# Vario_sch.net
KiCad netlist of a schematic drawn in Altium Designer
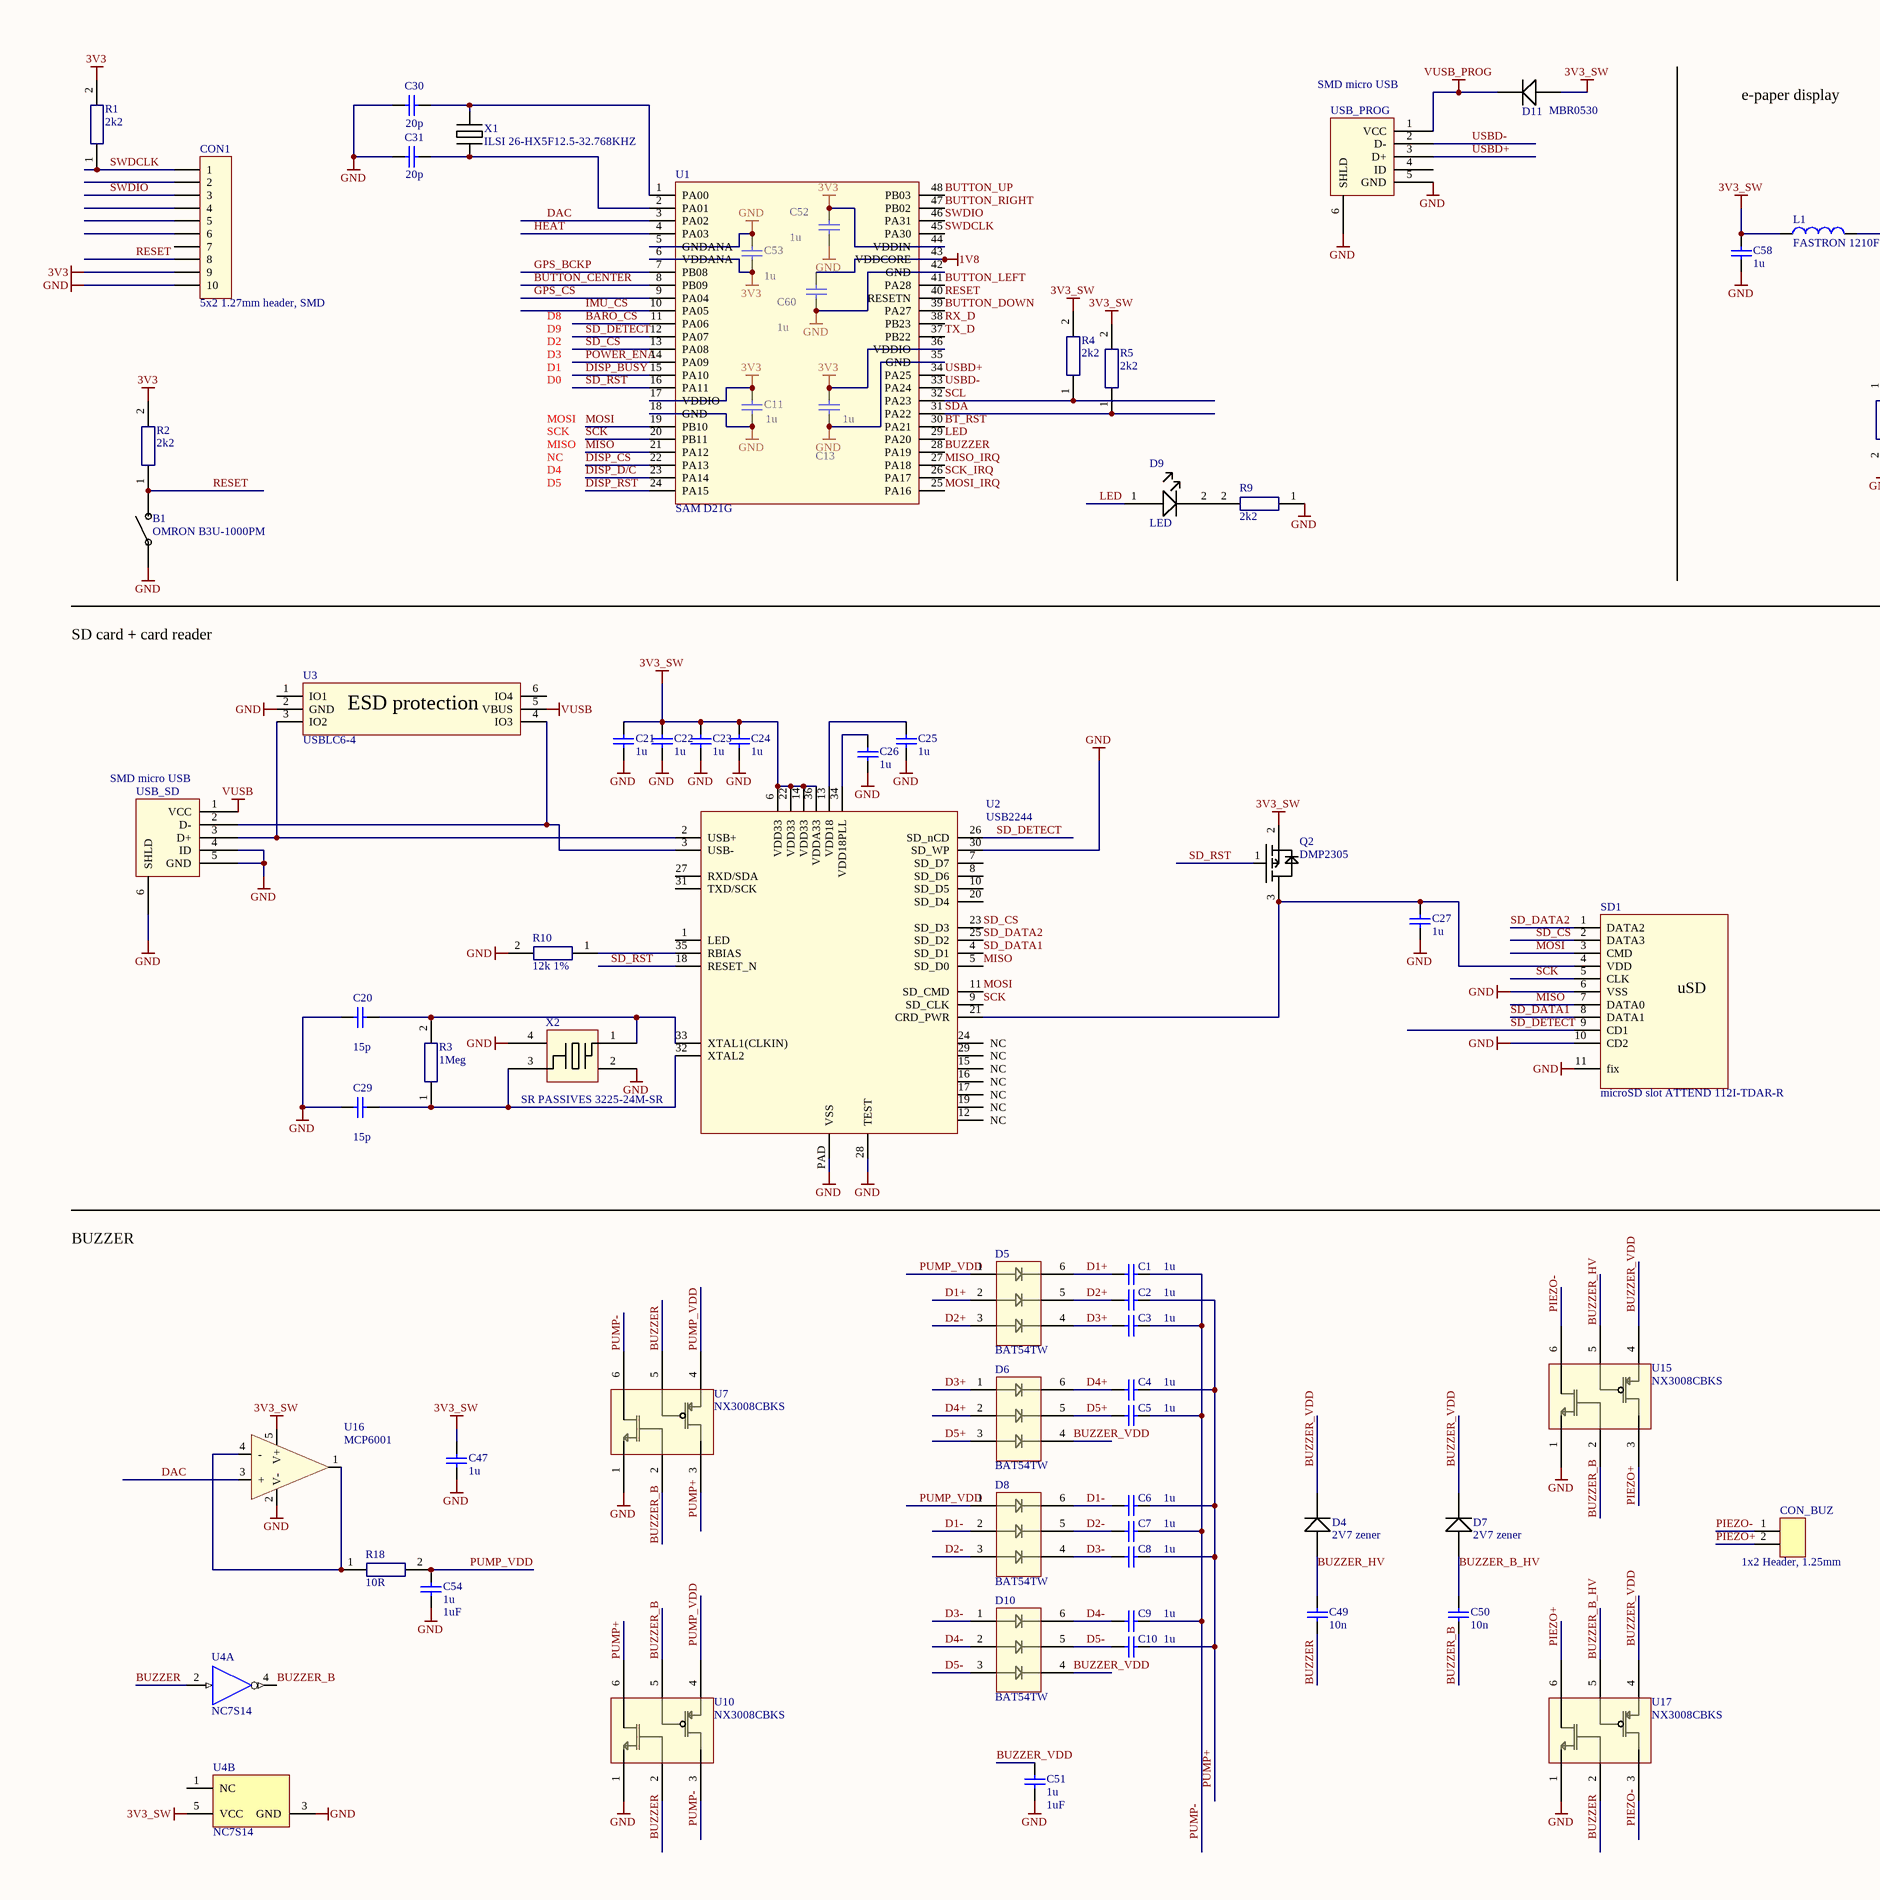
[diagram p0: Vario_sch.SchDoc, left]
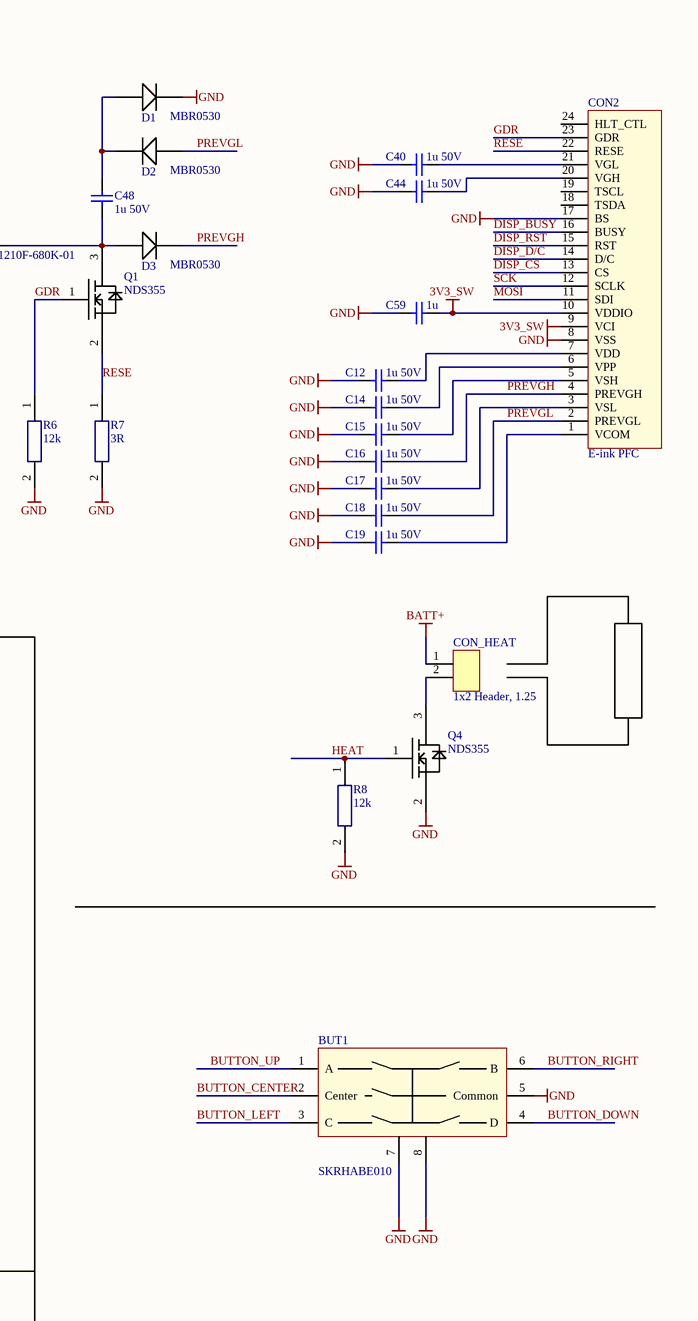
[diagram p1: Vario_sch.SchDoc, right]

(export (version "E")
  (design (tool "Eeschema 10.0.6"))
  (components
    (comp (ref "B1")
      (value "OMRON B3U-1000PM")
      (footprint "tlacitecko")
      (libsource (lib "xilinx") (part "Button"))
    )
    (comp (ref "BUT1")
      (value "SKRHABE010")
      (footprint "SKRHABE010")
      (description "5-way joystick")
      (libsource (lib "xilinx") (part "SKRHABE010"))
    )
    (comp (ref "C1")
      (value "1u")
      (footprint "cap0603")
      (description "0603")
      (fields (field (name "PUBLISHER") "Altium Limited"))
      (libsource (lib "Miscellaneous Devices") (part "Cap"))
    )
    (comp (ref "C2")
      (value "1u")
      (footprint "cap0603")
      (description "0603")
      (fields (field (name "PUBLISHER") "Altium Limited"))
      (libsource (lib "Miscellaneous Devices") (part "Cap"))
    )
    (comp (ref "C3")
      (value "1u")
      (footprint "cap0603")
      (description "0603")
      (fields (field (name "PUBLISHER") "Altium Limited"))
      (libsource (lib "Miscellaneous Devices") (part "Cap"))
    )
    (comp (ref "C4")
      (value "1u")
      (footprint "cap0603")
      (description "0603")
      (fields (field (name "PUBLISHER") "Altium Limited"))
      (libsource (lib "Miscellaneous Devices") (part "Cap"))
    )
    (comp (ref "C5")
      (value "1u")
      (footprint "cap0603")
      (description "0603")
      (fields (field (name "PUBLISHER") "Altium Limited"))
      (libsource (lib "Miscellaneous Devices") (part "Cap"))
    )
    (comp (ref "C6")
      (value "1u")
      (footprint "cap0603")
      (description "0603")
      (fields (field (name "PUBLISHER") "Altium Limited"))
      (libsource (lib "Miscellaneous Devices") (part "Cap"))
    )
    (comp (ref "C7")
      (value "1u")
      (footprint "cap0603")
      (description "0603")
      (fields (field (name "PUBLISHER") "Altium Limited"))
      (libsource (lib "Miscellaneous Devices") (part "Cap"))
    )
    (comp (ref "C8")
      (value "1u")
      (footprint "cap0603")
      (description "0603")
      (fields (field (name "PUBLISHER") "Altium Limited"))
      (libsource (lib "Miscellaneous Devices") (part "Cap"))
    )
    (comp (ref "C9")
      (value "1u")
      (footprint "cap0603")
      (description "0603")
      (fields (field (name "PUBLISHER") "Altium Limited"))
      (libsource (lib "Miscellaneous Devices") (part "Cap"))
    )
    (comp (ref "C10")
      (value "1u")
      (footprint "cap0603")
      (description "0603")
      (fields (field (name "PUBLISHER") "Altium Limited"))
      (libsource (lib "Miscellaneous Devices") (part "Cap"))
    )
    (comp (ref "C11")
      (value "1u")
      (footprint "cap0603")
      (description "0603")
      (fields (field (name "PUBLISHER") "Altium Limited"))
      (libsource (lib "Miscellaneous Devices") (part "Cap"))
    )
    (comp (ref "C12")
      (value "1u 50V")
      (footprint "cap0603")
      (description "0603")
      (fields (field (name "PUBLISHER") "Altium Limited"))
      (libsource (lib "Miscellaneous Devices") (part "Cap"))
    )
    (comp (ref "C13")
      (value "1u")
      (footprint "cap0603")
      (description "0603")
      (fields (field (name "PUBLISHER") "Altium Limited"))
      (libsource (lib "Miscellaneous Devices") (part "Cap"))
    )
    (comp (ref "C14")
      (value "1u 50V")
      (footprint "cap0603")
      (description "0603")
      (fields (field (name "PUBLISHER") "Altium Limited"))
      (libsource (lib "Miscellaneous Devices") (part "Cap"))
    )
    (comp (ref "C15")
      (value "1u 50V")
      (footprint "cap0603")
      (description "0603")
      (fields (field (name "PUBLISHER") "Altium Limited"))
      (libsource (lib "Miscellaneous Devices") (part "Cap"))
    )
    (comp (ref "C16")
      (value "1u 50V")
      (footprint "cap0603")
      (description "0603")
      (fields (field (name "PUBLISHER") "Altium Limited"))
      (libsource (lib "Miscellaneous Devices") (part "Cap"))
    )
    (comp (ref "C17")
      (value "1u 50V")
      (footprint "cap0603")
      (description "0603")
      (fields (field (name "PUBLISHER") "Altium Limited"))
      (libsource (lib "Miscellaneous Devices") (part "Cap"))
    )
    (comp (ref "C18")
      (value "1u 50V")
      (footprint "cap0603")
      (description "0603")
      (fields (field (name "PUBLISHER") "Altium Limited"))
      (libsource (lib "Miscellaneous Devices") (part "Cap"))
    )
    (comp (ref "C19")
      (value "1u 50V")
      (footprint "cap0603")
      (description "0603")
      (fields (field (name "PUBLISHER") "Altium Limited"))
      (libsource (lib "Miscellaneous Devices") (part "Cap"))
    )
    (comp (ref "C20")
      (value "15p")
      (footprint "cap0603")
      (description "0603")
      (fields (field (name "PUBLISHER") "Altium Limited"))
      (libsource (lib "Miscellaneous Devices") (part "Cap"))
    )
    (comp (ref "C21")
      (value "1u")
      (footprint "cap0603")
      (description "0603")
      (fields (field (name "PUBLISHER") "Altium Limited"))
      (libsource (lib "Miscellaneous Devices") (part "Cap"))
    )
    (comp (ref "C22")
      (value "1u")
      (footprint "cap0603")
      (description "0603")
      (fields (field (name "PUBLISHER") "Altium Limited"))
      (libsource (lib "Miscellaneous Devices") (part "Cap"))
    )
    (comp (ref "C23")
      (value "1u")
      (footprint "cap0603")
      (description "0603")
      (fields (field (name "PUBLISHER") "Altium Limited"))
      (libsource (lib "Miscellaneous Devices") (part "Cap"))
    )
    (comp (ref "C24")
      (value "1u")
      (footprint "cap0603")
      (description "0603")
      (fields (field (name "PUBLISHER") "Altium Limited"))
      (libsource (lib "Miscellaneous Devices") (part "Cap"))
    )
    (comp (ref "C25")
      (value "1u")
      (footprint "cap0603")
      (description "0603")
      (fields (field (name "PUBLISHER") "Altium Limited"))
      (libsource (lib "Miscellaneous Devices") (part "Cap"))
    )
    (comp (ref "C26")
      (value "1u")
      (footprint "cap0603")
      (description "0603")
      (fields (field (name "PUBLISHER") "Altium Limited"))
      (libsource (lib "Miscellaneous Devices") (part "Cap"))
    )
    (comp (ref "C27")
      (value "1u")
      (footprint "cap0603")
      (description "0603")
      (fields (field (name "PUBLISHER") "Altium Limited"))
      (libsource (lib "Miscellaneous Devices") (part "Cap"))
    )
    (comp (ref "C29")
      (value "15p")
      (footprint "cap0603")
      (description "0603")
      (fields (field (name "PUBLISHER") "Altium Limited"))
      (libsource (lib "Miscellaneous Devices") (part "Cap"))
    )
    (comp (ref "C30")
      (value "20p")
      (footprint "cap0603")
      (description "0603")
      (fields (field (name "PUBLISHER") "Altium Limited"))
      (libsource (lib "Miscellaneous Devices") (part "Cap"))
    )
    (comp (ref "C31")
      (value "20p")
      (footprint "cap0603")
      (description "0603")
      (fields (field (name "PUBLISHER") "Altium Limited"))
      (libsource (lib "Miscellaneous Devices") (part "Cap"))
    )
    (comp (ref "C40")
      (value "1u 50V")
      (footprint "cap0603")
      (description "0603")
      (fields (field (name "PUBLISHER") "Altium Limited"))
      (libsource (lib "Miscellaneous Devices") (part "Cap"))
    )
    (comp (ref "C44")
      (value "1u 50V")
      (footprint "cap0603")
      (description "0603")
      (fields (field (name "PUBLISHER") "Altium Limited"))
      (libsource (lib "Miscellaneous Devices") (part "Cap"))
    )
    (comp (ref "C47")
      (value "1u")
      (footprint "cap0603")
      (description "0603")
      (fields (field (name "PUBLISHER") "Altium Limited"))
      (libsource (lib "Miscellaneous Devices") (part "Cap"))
    )
    (comp (ref "C48")
      (value "1u 50V")
      (footprint "cap0603")
      (description "0603")
      (fields (field (name "PUBLISHER") "Altium Limited"))
      (libsource (lib "Miscellaneous Devices") (part "Cap"))
    )
    (comp (ref "C49")
      (value "10n")
      (footprint "cap0603")
      (description "0603")
      (fields (field (name "PUBLISHER") "Altium Limited"))
      (libsource (lib "Miscellaneous Devices") (part "Cap"))
    )
    (comp (ref "C50")
      (value "10n")
      (footprint "cap0603")
      (description "0603")
      (fields (field (name "PUBLISHER") "Altium Limited"))
      (libsource (lib "Miscellaneous Devices") (part "Cap"))
    )
    (comp (ref "C51")
      (value "1u")
      (footprint "cap0603")
      (description "0603")
      (fields (field (name "ALTIUM_VALUE") "1uF") (field (name "PUBLISHER") "Altium Limited"))
      (libsource (lib "Miscellaneous Devices") (part "Cap"))
    )
    (comp (ref "C52")
      (value "1u")
      (footprint "cap0603")
      (description "0603")
      (fields (field (name "PUBLISHER") "Altium Limited"))
      (libsource (lib "Miscellaneous Devices") (part "Cap"))
    )
    (comp (ref "C53")
      (value "1u")
      (footprint "cap0603")
      (description "0603")
      (fields (field (name "PUBLISHER") "Altium Limited"))
      (libsource (lib "Miscellaneous Devices") (part "Cap"))
    )
    (comp (ref "C54")
      (value "1u")
      (footprint "cap0603")
      (description "0603")
      (fields (field (name "ALTIUM_VALUE") "1uF") (field (name "PUBLISHER") "Altium Limited"))
      (libsource (lib "Miscellaneous Devices") (part "Cap"))
    )
    (comp (ref "C58")
      (value "1u")
      (footprint "cap0603")
      (description "0603")
      (fields (field (name "PUBLISHER") "Altium Limited"))
      (libsource (lib "Miscellaneous Devices") (part "Cap"))
    )
    (comp (ref "C59")
      (value "1u")
      (footprint "cap0603")
      (description "0603")
      (fields (field (name "PUBLISHER") "Altium Limited"))
      (libsource (lib "Miscellaneous Devices") (part "Cap"))
    )
    (comp (ref "C60")
      (value "1u")
      (footprint "cap0603")
      (description "0603")
      (fields (field (name "PUBLISHER") "Altium Limited"))
      (libsource (lib "Miscellaneous Devices") (part "Cap"))
    )
    (comp (ref "CON1")
      (value "5x2 1.27mm header, SMD")
      (footprint "2x5, 1.27, SMD")
      (description "programming connector for uC")
      (libsource (lib "xilinx") (part "5x2 1.27mm"))
    )
    (comp (ref "CON2")
      (value "E-ink PFC")
      (footprint "24 way PFC connector")
      (description "OMRON XF2W24151AR100")
      (libsource (lib "xilinx") (part "E-ink PFC"))
    )
    (comp (ref "CON_BUZ")
      (value "1x2 Header, 1.25mm")
      (footprint "1x2, 1.25")
      (libsource (lib "headers") (part "1x2 Header, 2.54"))
    )
    (comp (ref "CON_HEAT")
      (value "1x2 Header, 1.25")
      (footprint "1x2, 1.25")
      (description "90deg angle")
      (libsource (lib "headers") (part "1x2 Header, 2.54"))
    )
    (comp (ref "D1")
      (value "MBR0530")
      (footprint "MiniMELF")
      (description "SOD−123 shottky diode")
      (libsource (lib "xilinx") (part "DB27308"))
    )
    (comp (ref "D2")
      (value "MBR0530")
      (footprint "MiniMELF")
      (description "SOD−123 shottky diode")
      (libsource (lib "xilinx") (part "DB27308"))
    )
    (comp (ref "D3")
      (value "MBR0530")
      (footprint "MiniMELF")
      (description "SOD−123 shottky diode")
      (libsource (lib "xilinx") (part "DB27308"))
    )
    (comp (ref "D4")
      (value "2V7 zener")
      (footprint "Micromelf")
      (description "micromelf")
      (libsource (lib "xilinx") (part "DB27308"))
    )
    (comp (ref "D5") (value "BAT54TW") (footprint "SC70") (libsource (lib "xilinx") (part "BAT54TW")))
    (comp (ref "D6") (value "BAT54TW") (footprint "SC70") (libsource (lib "xilinx") (part "BAT54TW")))
    (comp (ref "D7")
      (value "2V7 zener")
      (footprint "Micromelf")
      (description "micromelf")
      (libsource (lib "xilinx") (part "DB27308"))
    )
    (comp (ref "D8") (value "BAT54TW") (footprint "SC70") (libsource (lib "xilinx") (part "BAT54TW")))
    (comp (ref "D9") (value "LED") (footprint "cap0805") (libsource (lib "xilinx") (part "LED")))
    (comp (ref "D10") (value "BAT54TW") (footprint "SC70") (libsource (lib "xilinx") (part "BAT54TW")))
    (comp (ref "D11")
      (value "MBR0530")
      (footprint "MiniMELF")
      (description "SOD−123 shottky diode")
      (libsource (lib "xilinx") (part "DB27308"))
    )
    (comp (ref "L1")
      (value "FASTRON 1210F-680K-01")
      (footprint "res1206")
      (description "1210F-680K-01")
      (libsource (lib "PassiveSMT") (part "Inductor1"))
    )
    (comp (ref "Q1")
      (value "NDS355")
      (footprint "sot23-3")
      (description "N-FET transistor")
      (libsource (lib "xilinx") (part "BSS138"))
    )
    (comp (ref "Q2")
      (value "DMP2305")
      (footprint "sot23-3")
      (description "P-FET transistor")
      (libsource (lib "xilinx") (part "NX3008"))
    )
    (comp (ref "Q4")
      (value "NDS355")
      (footprint "sot23-3")
      (description "N-FET transistor")
      (libsource (lib "xilinx") (part "BSS138"))
    )
    (comp (ref "R1")
      (value "2k2")
      (footprint "cap0805")
      (description "0805")
      (libsource (lib "PassiveSMT") (part "Resistor1"))
    )
    (comp (ref "R2")
      (value "2k2")
      (footprint "cap0805")
      (description "0805")
      (libsource (lib "PassiveSMT") (part "Resistor1"))
    )
    (comp (ref "R3")
      (value "1Meg")
      (footprint "cap0805")
      (description "0805")
      (libsource (lib "PassiveSMT") (part "Resistor1"))
    )
    (comp (ref "R4")
      (value "2k2")
      (footprint "cap0805")
      (description "0805")
      (libsource (lib "PassiveSMT") (part "Resistor1"))
    )
    (comp (ref "R5")
      (value "2k2")
      (footprint "cap0805")
      (description "0805")
      (libsource (lib "PassiveSMT") (part "Resistor1"))
    )
    (comp (ref "R6")
      (value "12k")
      (footprint "cap0805")
      (description "0805")
      (libsource (lib "PassiveSMT") (part "Resistor1"))
    )
    (comp (ref "R7")
      (value "3R")
      (footprint "cap0805")
      (description "0805")
      (libsource (lib "PassiveSMT") (part "Resistor1"))
    )
    (comp (ref "R8")
      (value "12k")
      (footprint "cap0805")
      (description "0805")
      (libsource (lib "PassiveSMT") (part "Resistor1"))
    )
    (comp (ref "R9")
      (value "2k2")
      (footprint "cap0805")
      (description "0805")
      (libsource (lib "PassiveSMT") (part "Resistor1"))
    )
    (comp (ref "R10")
      (value "12k 1%")
      (footprint "cap0805")
      (description "0805")
      (libsource (lib "PassiveSMT") (part "Resistor1"))
    )
    (comp (ref "R18")
      (value "10R")
      (footprint "cap0805")
      (description "0805")
      (libsource (lib "PassiveSMT") (part "Resistor1"))
    )
    (comp (ref "SD1")
      (value "microSD slot ATTEND 112I-TDAR-R")
      (footprint "microSD_slot")
      (description "ATTEND 112I-TDAR-R")
      (libsource (lib "xilinx") (part "microSD slot"))
    )
    (comp (ref "U1")
      (value "SAM D21G")
      (footprint "48QFP 0.5mm")
      (description "Atmel ARM M0+ uC")
      (libsource (lib "xilinx") (part "SAM D21G"))
    )
    (comp (ref "U2")
      (value "USB2244")
      (footprint "qfn36")
      (description "SD card reader")
      (libsource (lib "xilinx") (part "USB2244"))
    )
    (comp (ref "U3")
      (value "USBLC6-4")
      (footprint "sot23-6")
      (description "ESD protection")
      (libsource (lib "xilinx") (part "USBLC6-4"))
    )
    (comp (ref "U4")
      (value "NC7S14")
      (footprint "sot23-5")
      (description "SOT23-5 single Inverter")
      (fields
        (field (name "GENERIC PART NUMBER") "SN74LVC1G04")
        (field (name "MANUFACTURER") "Texas Instruments")
      )
      (libsource (lib "TI_Logic_Little_Logic") (part "SN74LVC1G04DBVR"))
    )
    (comp (ref "U7")
      (value "NX3008CBKS")
      (footprint "SC70")
      (description "SC70 N/P dual mos")
      (libsource (lib "xilinx") (part "NX3008CBKS"))
    )
    (comp (ref "U10")
      (value "NX3008CBKS")
      (footprint "SC70")
      (description "SC70 N/P dual mos")
      (libsource (lib "xilinx") (part "NX3008CBKS"))
    )
    (comp (ref "U15")
      (value "NX3008CBKS")
      (footprint "SC70")
      (description "SC70 N/P dual mos")
      (libsource (lib "xilinx") (part "NX3008CBKS"))
    )
    (comp (ref "U16")
      (value "MCP6001")
      (footprint "sot23-5")
      (description "SOT23 R-R opamp")
      (libsource (lib "xilinx") (part "MCP601"))
    )
    (comp (ref "U17")
      (value "NX3008CBKS")
      (footprint "SC70")
      (description "SC70 N/P dual mos")
      (libsource (lib "xilinx") (part "NX3008CBKS"))
    )
    (comp (ref "USB_PROG")
      (value "SMD micro USB")
      (footprint "microusb_smd")
      (libsource (lib "xilinx") (part "micro USB"))
    )
    (comp (ref "USB_SD")
      (value "SMD micro USB")
      (footprint "microusb_smd")
      (libsource (lib "xilinx") (part "micro USB"))
    )
    (comp (ref "X1")
      (value "ILSI 26-HX5F12.5-32.768KHZ")
      (footprint "crystal")
      (libsource (lib "xilinx") (part "Crystal"))
    )
    (comp (ref "X2")
      (value "SR PASSIVES 3225-24M-SR")
      (footprint "crystal 3.2x2.5")
      (libsource (lib "xilinx") (part "Crystal_smd"))
    )
  )
  (nets
    (net (code "1") (name "/BARO_CS") (class "Default")
      (node (ref "U1") (pin "11") (pinfunction "PA06_11") (pintype "passive"))
    )
    (net (code "2") (name "/BT_RST") (class "Default")
      (node (ref "U1") (pin "30") (pinfunction "PA21_30") (pintype "passive"))
    )
    (net (code "3") (name "/BUTTON_CENTER") (class "Default")
      (node (ref "BUT1") (pin "2") (pinfunction "Center_2") (pintype "passive"))
      (node (ref "U1") (pin "8") (pinfunction "PB09_8") (pintype "passive"))
    )
    (net (code "4") (name "/BUTTON_DOWN") (class "Default")
      (node (ref "BUT1") (pin "4") (pinfunction "D_4") (pintype "passive"))
      (node (ref "U1") (pin "39") (pinfunction "PA27_39") (pintype "passive"))
    )
    (net (code "5") (name "/BUTTON_LEFT") (class "Default")
      (node (ref "BUT1") (pin "3") (pinfunction "C_3") (pintype "passive"))
      (node (ref "U1") (pin "41") (pinfunction "PA28_41") (pintype "passive"))
    )
    (net (code "6") (name "/BUTTON_RIGHT") (class "Default")
      (node (ref "BUT1") (pin "6") (pinfunction "B_6") (pintype "passive"))
      (node (ref "U1") (pin "47") (pinfunction "PB02_47") (pintype "passive"))
    )
    (net (code "7") (name "/BUTTON_UP") (class "Default")
      (node (ref "BUT1") (pin "1") (pinfunction "A_1") (pintype "passive"))
      (node (ref "U1") (pin "48") (pinfunction "PB03_48") (pintype "passive"))
    )
    (net (code "8") (name "/BUZZER") (class "Default")
      (node (ref "C49") (pin "2") (pinfunction "2_2") (pintype "passive"))
      (node (ref "U1") (pin "28") (pinfunction "PA19_28") (pintype "passive"))
      (node (ref "U10") (pin "2") (pinfunction "2_2") (pintype "passive"))
      (node (ref "U17") (pin "2") (pinfunction "2_2") (pintype "passive"))
      (node (ref "U4") (pin "2") (pinfunction "A_2") (pintype "input"))
      (node (ref "U7") (pin "5") (pinfunction "5_5") (pintype "passive"))
    )
    (net (code "9") (name "/BUZZER_B") (class "Default")
      (node (ref "C50") (pin "2") (pinfunction "2_2") (pintype "passive"))
      (node (ref "U10") (pin "5") (pinfunction "5_5") (pintype "passive"))
      (node (ref "U15") (pin "2") (pinfunction "2_2") (pintype "passive"))
      (node (ref "U4") (pin "4") (pinfunction "Y_4") (pintype "output"))
      (node (ref "U7") (pin "2") (pinfunction "2_2") (pintype "passive"))
    )
    (net (code "10") (name "/BUZZER_B_HV") (class "Default")
      (node (ref "C50") (pin "1") (pinfunction "1_1") (pintype "passive"))
      (node (ref "D7") (pin "A") (pinfunction "A_A") (pintype "passive"))
      (node (ref "U17") (pin "5") (pinfunction "5_5") (pintype "passive"))
    )
    (net (code "11") (name "/BUZZER_HV") (class "Default")
      (node (ref "C49") (pin "1") (pinfunction "1_1") (pintype "passive"))
      (node (ref "D4") (pin "A") (pinfunction "A_A") (pintype "passive"))
      (node (ref "U15") (pin "5") (pinfunction "5_5") (pintype "passive"))
    )
    (net (code "12") (name "/BUZZER_VDD") (class "Default")
      (node (ref "C51") (pin "1") (pinfunction "1_1") (pintype "passive"))
      (node (ref "D10") (pin "4") (pinfunction "4_4") (pintype "passive"))
      (node (ref "D4") (pin "K") (pinfunction "K_K") (pintype "passive"))
      (node (ref "D6") (pin "4") (pinfunction "4_4") (pintype "passive"))
      (node (ref "D7") (pin "K") (pinfunction "K_K") (pintype "passive"))
      (node (ref "U15") (pin "4") (pinfunction "4_4") (pintype "passive"))
      (node (ref "U17") (pin "4") (pinfunction "4_4") (pintype "passive"))
    )
    (net (code "13") (name "/D1+") (class "Default")
      (node (ref "C1") (pin "1") (pinfunction "1_1") (pintype "passive"))
      (node (ref "D5") (pin "2") (pinfunction "2_2") (pintype "passive"))
      (node (ref "D5") (pin "6") (pinfunction "6_6") (pintype "passive"))
    )
    (net (code "14") (name "/D1-") (class "Default")
      (node (ref "C6") (pin "1") (pinfunction "1_1") (pintype "passive"))
      (node (ref "D8") (pin "2") (pinfunction "2_2") (pintype "passive"))
      (node (ref "D8") (pin "6") (pinfunction "6_6") (pintype "passive"))
    )
    (net (code "15") (name "/D2+") (class "Default")
      (node (ref "C2") (pin "1") (pinfunction "1_1") (pintype "passive"))
      (node (ref "D5") (pin "3") (pinfunction "3_3") (pintype "passive"))
      (node (ref "D5") (pin "5") (pinfunction "5_5") (pintype "passive"))
    )
    (net (code "16") (name "/D2-") (class "Default")
      (node (ref "C7") (pin "1") (pinfunction "1_1") (pintype "passive"))
      (node (ref "D8") (pin "3") (pinfunction "3_3") (pintype "passive"))
      (node (ref "D8") (pin "5") (pinfunction "5_5") (pintype "passive"))
    )
    (net (code "17") (name "/D3+") (class "Default")
      (node (ref "C3") (pin "1") (pinfunction "1_1") (pintype "passive"))
      (node (ref "D5") (pin "4") (pinfunction "4_4") (pintype "passive"))
      (node (ref "D6") (pin "1") (pinfunction "1_1") (pintype "passive"))
    )
    (net (code "18") (name "/D3-") (class "Default")
      (node (ref "C8") (pin "1") (pinfunction "1_1") (pintype "passive"))
      (node (ref "D10") (pin "1") (pinfunction "1_1") (pintype "passive"))
      (node (ref "D8") (pin "4") (pinfunction "4_4") (pintype "passive"))
    )
    (net (code "19") (name "/D4+") (class "Default")
      (node (ref "C4") (pin "1") (pinfunction "1_1") (pintype "passive"))
      (node (ref "D6") (pin "2") (pinfunction "2_2") (pintype "passive"))
      (node (ref "D6") (pin "6") (pinfunction "6_6") (pintype "passive"))
    )
    (net (code "20") (name "/D4-") (class "Default")
      (node (ref "C9") (pin "1") (pinfunction "1_1") (pintype "passive"))
      (node (ref "D10") (pin "2") (pinfunction "2_2") (pintype "passive"))
      (node (ref "D10") (pin "6") (pinfunction "6_6") (pintype "passive"))
    )
    (net (code "21") (name "/D5+") (class "Default")
      (node (ref "C5") (pin "1") (pinfunction "1_1") (pintype "passive"))
      (node (ref "D6") (pin "3") (pinfunction "3_3") (pintype "passive"))
      (node (ref "D6") (pin "5") (pinfunction "5_5") (pintype "passive"))
    )
    (net (code "22") (name "/D5-") (class "Default")
      (node (ref "C10") (pin "1") (pinfunction "1_1") (pintype "passive"))
      (node (ref "D10") (pin "3") (pinfunction "3_3") (pintype "passive"))
      (node (ref "D10") (pin "5") (pinfunction "5_5") (pintype "passive"))
    )
    (net (code "23") (name "/DAC") (class "Default")
      (node (ref "U1") (pin "3") (pinfunction "PA02_3") (pintype "passive"))
      (node (ref "U16") (pin "3") (pinfunction "+_3") (pintype "passive"))
    )
    (net (code "24") (name "/DISP_BUSY") (class "Default")
      (node (ref "CON2") (pin "16") (pinfunction "BUSY_16") (pintype "passive"))
      (node (ref "U1") (pin "15") (pinfunction "PA10_15") (pintype "passive"))
    )
    (net (code "25") (name "/DISP_CS") (class "Default")
      (node (ref "CON2") (pin "13") (pinfunction "CS_13") (pintype "passive"))
      (node (ref "U1") (pin "22") (pinfunction "PA13_22") (pintype "passive"))
    )
    (net (code "26") (name "/DISP_D{slash}C") (class "Default")
      (node (ref "CON2") (pin "14") (pinfunction "D/C_14") (pintype "passive"))
      (node (ref "U1") (pin "23") (pinfunction "PA14_23") (pintype "passive"))
    )
    (net (code "27") (name "/DISP_RST") (class "Default")
      (node (ref "CON2") (pin "15") (pinfunction "RST_15") (pintype "passive"))
      (node (ref "U1") (pin "24") (pinfunction "PA15_24") (pintype "passive"))
    )
    (net (code "28") (name "/GDR") (class "Default")
      (node (ref "CON2") (pin "23") (pinfunction "GDR_23") (pintype "passive"))
      (node (ref "Q1") (pin "1") (pinfunction "G_1") (pintype "passive"))
      (node (ref "R6") (pin "1") (pinfunction "1_1") (pintype "passive"))
    )
    (net (code "29") (name "/GPS_BCKP") (class "Default")
      (node (ref "U1") (pin "7") (pinfunction "PB08_7") (pintype "passive"))
    )
    (net (code "30") (name "/GPS_CS") (class "Default")
      (node (ref "U1") (pin "9") (pinfunction "PA04_9") (pintype "passive"))
    )
    (net (code "31") (name "/HEAT") (class "Default")
      (node (ref "Q4") (pin "1") (pinfunction "G_1") (pintype "passive"))
      (node (ref "R8") (pin "1") (pinfunction "1_1") (pintype "passive"))
      (node (ref "U1") (pin "4") (pinfunction "PA03_4") (pintype "passive"))
    )
    (net (code "32") (name "/IMU_CS") (class "Default")
      (node (ref "U1") (pin "10") (pinfunction "PA05_10") (pintype "passive"))
    )
    (net (code "33") (name "/LED") (class "Default")
      (node (ref "D9") (pin "1") (pinfunction "1_1") (pintype "passive"))
      (node (ref "U1") (pin "29") (pinfunction "PA20_29") (pintype "passive"))
    )
    (net (code "34") (name "/MISO") (class "Default")
      (node (ref "SD1") (pin "7") (pinfunction "DATA0_7") (pintype "passive"))
      (node (ref "U1") (pin "21") (pinfunction "PA12_21") (pintype "passive"))
      (node (ref "U2") (pin "5") (pinfunction "SD_D0_5") (pintype "passive"))
    )
    (net (code "35") (name "/MISO_IRQ") (class "Default")
      (node (ref "U1") (pin "27") (pinfunction "PA18_27") (pintype "passive"))
    )
    (net (code "36") (name "/MOSI") (class "Default")
      (node (ref "CON2") (pin "11") (pinfunction "SDI_11") (pintype "passive"))
      (node (ref "SD1") (pin "3") (pinfunction "CMD_3") (pintype "passive"))
      (node (ref "U1") (pin "19") (pinfunction "PB10_19") (pintype "passive"))
      (node (ref "U2") (pin "11") (pinfunction "SD_CMD_11") (pintype "passive"))
    )
    (net (code "37") (name "/MOSI_IRQ") (class "Default")
      (node (ref "U1") (pin "25") (pinfunction "PA16_25") (pintype "passive"))
    )
    (net (code "38") (name "/PIEZO+") (class "Default")
      (node (ref "CON_BUZ") (pin "2") (pinfunction "2_2") (pintype "passive"))
      (node (ref "U15") (pin "3") (pinfunction "3_3") (pintype "passive"))
      (node (ref "U17") (pin "6") (pinfunction "6_6") (pintype "passive"))
    )
    (net (code "39") (name "/PIEZO-") (class "Default")
      (node (ref "CON_BUZ") (pin "1") (pinfunction "1_1") (pintype "passive"))
      (node (ref "U15") (pin "6") (pinfunction "6_6") (pintype "passive"))
      (node (ref "U17") (pin "3") (pinfunction "3_3") (pintype "passive"))
    )
    (net (code "40") (name "/POWER_ENA") (class "Default")
      (node (ref "U1") (pin "14") (pinfunction "PA09_14") (pintype "passive"))
    )
    (net (code "41") (name "/PREVGH") (class "Default")
      (node (ref "C16") (pin "2") (pinfunction "2_2") (pintype "passive"))
      (node (ref "CON2") (pin "4") (pinfunction "PREVGH_4") (pintype "passive"))
      (node (ref "D3") (pin "K") (pinfunction "K_K") (pintype "passive"))
    )
    (net (code "42") (name "/PREVGL") (class "Default")
      (node (ref "C18") (pin "2") (pinfunction "2_2") (pintype "passive"))
      (node (ref "CON2") (pin "2") (pinfunction "PREVGL_2") (pintype "passive"))
      (node (ref "D2") (pin "A") (pinfunction "A_A") (pintype "passive"))
    )
    (net (code "43") (name "/PUMP+") (class "Default")
      (node (ref "C10") (pin "2") (pinfunction "2_2") (pintype "passive"))
      (node (ref "C2") (pin "2") (pinfunction "2_2") (pintype "passive"))
      (node (ref "C4") (pin "2") (pinfunction "2_2") (pintype "passive"))
      (node (ref "C6") (pin "2") (pinfunction "2_2") (pintype "passive"))
      (node (ref "C8") (pin "2") (pinfunction "2_2") (pintype "passive"))
      (node (ref "U10") (pin "6") (pinfunction "6_6") (pintype "passive"))
      (node (ref "U7") (pin "3") (pinfunction "3_3") (pintype "passive"))
    )
    (net (code "44") (name "/PUMP-") (class "Default")
      (node (ref "C1") (pin "2") (pinfunction "2_2") (pintype "passive"))
      (node (ref "C3") (pin "2") (pinfunction "2_2") (pintype "passive"))
      (node (ref "C5") (pin "2") (pinfunction "2_2") (pintype "passive"))
      (node (ref "C7") (pin "2") (pinfunction "2_2") (pintype "passive"))
      (node (ref "C9") (pin "2") (pinfunction "2_2") (pintype "passive"))
      (node (ref "U10") (pin "3") (pinfunction "3_3") (pintype "passive"))
      (node (ref "U7") (pin "6") (pinfunction "6_6") (pintype "passive"))
    )
    (net (code "45") (name "/PUMP_VDD") (class "Default")
      (node (ref "C54") (pin "1") (pinfunction "1_1") (pintype "passive"))
      (node (ref "D5") (pin "1") (pinfunction "1_1") (pintype "passive"))
      (node (ref "D8") (pin "1") (pinfunction "1_1") (pintype "passive"))
      (node (ref "R18") (pin "2") (pinfunction "2_2") (pintype "passive"))
      (node (ref "U10") (pin "4") (pinfunction "4_4") (pintype "passive"))
      (node (ref "U7") (pin "4") (pinfunction "4_4") (pintype "passive"))
    )
    (net (code "46") (name "/RESE") (class "Default")
      (node (ref "CON2") (pin "22") (pinfunction "RESE_22") (pintype "passive"))
      (node (ref "Q1") (pin "2") (pinfunction "D_2") (pintype "passive"))
      (node (ref "R7") (pin "1") (pinfunction "1_1") (pintype "passive"))
    )
    (net (code "47") (name "/RESET") (class "Default")
      (node (ref "B1") (pin "2") (pinfunction "2_2") (pintype "passive"))
      (node (ref "CON1") (pin "8") (pinfunction "8_8") (pintype "passive"))
      (node (ref "R2") (pin "1") (pinfunction "1_1") (pintype "passive"))
      (node (ref "U1") (pin "40") (pinfunction "RESETN_40") (pintype "passive"))
    )
    (net (code "48") (name "/RX_D") (class "Default")
      (node (ref "U1") (pin "38") (pinfunction "PB23_38") (pintype "passive"))
    )
    (net (code "49") (name "/SCK") (class "Default")
      (node (ref "CON2") (pin "12") (pinfunction "SCLK_12") (pintype "passive"))
      (node (ref "SD1") (pin "5") (pinfunction "CLK_5") (pintype "passive"))
      (node (ref "U1") (pin "20") (pinfunction "PB11_20") (pintype "passive"))
      (node (ref "U2") (pin "9") (pinfunction "SD_CLK_9") (pintype "passive"))
    )
    (net (code "50") (name "/SCK_IRQ") (class "Default")
      (node (ref "U1") (pin "26") (pinfunction "PA17_26") (pintype "passive"))
    )
    (net (code "51") (name "/SCL") (class "Default")
      (node (ref "R4") (pin "1") (pinfunction "1_1") (pintype "passive"))
      (node (ref "U1") (pin "32") (pinfunction "PA23_32") (pintype "passive"))
    )
    (net (code "52") (name "/SDA") (class "Default")
      (node (ref "R5") (pin "1") (pinfunction "1_1") (pintype "passive"))
      (node (ref "U1") (pin "31") (pinfunction "PA22_31") (pintype "passive"))
    )
    (net (code "53") (name "/SD_CS") (class "Default")
      (node (ref "SD1") (pin "2") (pinfunction "DATA3_2") (pintype "passive"))
      (node (ref "U1") (pin "13") (pinfunction "PA08_13") (pintype "passive"))
      (node (ref "U2") (pin "23") (pinfunction "SD_D3_23") (pintype "passive"))
    )
    (net (code "54") (name "/SD_DATA1") (class "Default")
      (node (ref "SD1") (pin "8") (pinfunction "DATA1_8") (pintype "passive"))
      (node (ref "U2") (pin "4") (pinfunction "SD_D1_4") (pintype "passive"))
    )
    (net (code "55") (name "/SD_DATA2") (class "Default")
      (node (ref "SD1") (pin "1") (pinfunction "DATA2_1") (pintype "passive"))
      (node (ref "U2") (pin "25") (pinfunction "SD_D2_25") (pintype "passive"))
    )
    (net (code "56") (name "/SD_DETECT") (class "Default")
      (node (ref "SD1") (pin "9") (pinfunction "CD1_9") (pintype "passive"))
      (node (ref "U1") (pin "12") (pinfunction "PA07_12") (pintype "passive"))
      (node (ref "U2") (pin "26") (pinfunction "SD_nCD_26") (pintype "passive"))
    )
    (net (code "57") (name "/SD_RST") (class "Default")
      (node (ref "Q2") (pin "1") (pinfunction "G_1") (pintype "passive"))
      (node (ref "U1") (pin "16") (pinfunction "PA11_16") (pintype "passive"))
      (node (ref "U2") (pin "18") (pinfunction "RESET_N_18") (pintype "passive"))
    )
    (net (code "58") (name "/SWDCLK") (class "Default")
      (node (ref "CON1") (pin "1") (pinfunction "1_1") (pintype "passive"))
      (node (ref "R1") (pin "1") (pinfunction "1_1") (pintype "passive"))
      (node (ref "U1") (pin "45") (pinfunction "PA30_45") (pintype "passive"))
    )
    (net (code "59") (name "/SWDIO") (class "Default")
      (node (ref "CON1") (pin "3") (pinfunction "3_3") (pintype "passive"))
      (node (ref "U1") (pin "46") (pinfunction "PA31_46") (pintype "passive"))
    )
    (net (code "60") (name "/TX_D") (class "Default")
      (node (ref "U1") (pin "37") (pinfunction "PB22_37") (pintype "passive"))
    )
    (net (code "61") (name "/USBD+") (class "Default")
      (node (ref "U1") (pin "34") (pinfunction "PA25_34") (pintype "passive"))
      (node (ref "USB_PROG") (pin "3") (pinfunction "D+_3") (pintype "passive"))
    )
    (net (code "62") (name "/USBD-") (class "Default")
      (node (ref "U1") (pin "33") (pinfunction "PA24_33") (pintype "passive"))
      (node (ref "USB_PROG") (pin "2") (pinfunction "D-_2") (pintype "passive"))
    )
    (net (code "63") (name "1V8") (class "Default")
      (node (ref "C60") (pin "2") (pinfunction "2_2") (pintype "passive"))
      (node (ref "U1") (pin "43") (pinfunction "VDDCORE_43") (pintype "passive"))
    )
    (net (code "64") (name "3V3") (class "Default")
      (node (ref "C11") (pin "2") (pinfunction "2_2") (pintype "passive"))
      (node (ref "C13") (pin "2") (pinfunction "2_2") (pintype "passive"))
      (node (ref "C52") (pin "1") (pinfunction "1_1") (pintype "passive"))
      (node (ref "C53") (pin "2") (pinfunction "2_2") (pintype "passive"))
      (node (ref "CON1") (pin "9") (pinfunction "9_9") (pintype "passive"))
      (node (ref "R1") (pin "2") (pinfunction "2_2") (pintype "passive"))
      (node (ref "R2") (pin "2") (pinfunction "2_2") (pintype "passive"))
      (node (ref "U1") (pin "17") (pinfunction "VDDIO_17") (pintype "passive"))
      (node (ref "U1") (pin "36") (pinfunction "VDDIO_36") (pintype "passive"))
      (node (ref "U1") (pin "44") (pinfunction "VDDIN_44") (pintype "passive"))
      (node (ref "U1") (pin "6") (pinfunction "VDDANA_6") (pintype "passive"))
    )
    (net (code "65") (name "3V3_SW") (class "Default")
      (node (ref "C21") (pin "2") (pinfunction "2_2") (pintype "passive"))
      (node (ref "C22") (pin "2") (pinfunction "2_2") (pintype "passive"))
      (node (ref "C23") (pin "2") (pinfunction "2_2") (pintype "passive"))
      (node (ref "C24") (pin "2") (pinfunction "2_2") (pintype "passive"))
      (node (ref "C47") (pin "2") (pinfunction "2_2") (pintype "passive"))
      (node (ref "C58") (pin "2") (pinfunction "2_2") (pintype "passive"))
      (node (ref "C59") (pin "2") (pinfunction "2_2") (pintype "passive"))
      (node (ref "CON2") (pin "10") (pinfunction "VDDIO_10") (pintype "passive"))
      (node (ref "CON2") (pin "9") (pinfunction "VCI_9") (pintype "passive"))
      (node (ref "D11") (pin "A") (pinfunction "A_A") (pintype "passive"))
      (node (ref "L1") (pin "1") (pinfunction "1_1") (pintype "passive"))
      (node (ref "Q2") (pin "2") (pinfunction "S_2") (pintype "passive"))
      (node (ref "R4") (pin "2") (pinfunction "2_2") (pintype "passive"))
      (node (ref "R5") (pin "2") (pinfunction "2_2") (pintype "passive"))
      (node (ref "U16") (pin "5") (pinfunction "V+_5") (pintype "passive"))
      (node (ref "U2") (pin "14") (pinfunction "VDD33_14") (pintype "passive"))
      (node (ref "U2") (pin "22") (pinfunction "VDD33_22") (pintype "passive"))
      (node (ref "U2") (pin "36") (pinfunction "VDDA33_36") (pintype "passive"))
      (node (ref "U2") (pin "6") (pinfunction "VDD33_6") (pintype "passive"))
      (node (ref "U4") (pin "5") (pinfunction "VCC_5") (pintype "power_in"))
    )
    (net (code "66") (name "BATT+") (class "Default")
      (node (ref "CON_HEAT") (pin "1") (pinfunction "1_1") (pintype "passive"))
    )
    (net (code "67") (name "GND") (class "Default")
      (node (ref "B1") (pin "1") (pinfunction "1_1") (pintype "passive"))
      (node (ref "BUT1") (pin "5") (pinfunction "Common_5") (pintype "passive"))
      (node (ref "BUT1") (pin "7") (pinfunction "7_7") (pintype "passive"))
      (node (ref "BUT1") (pin "8") (pinfunction "8_8") (pintype "passive"))
      (node (ref "C11") (pin "1") (pinfunction "1_1") (pintype "passive"))
      (node (ref "C12") (pin "1") (pinfunction "1_1") (pintype "passive"))
      (node (ref "C13") (pin "1") (pinfunction "1_1") (pintype "passive"))
      (node (ref "C14") (pin "1") (pinfunction "1_1") (pintype "passive"))
      (node (ref "C15") (pin "1") (pinfunction "1_1") (pintype "passive"))
      (node (ref "C16") (pin "1") (pinfunction "1_1") (pintype "passive"))
      (node (ref "C17") (pin "1") (pinfunction "1_1") (pintype "passive"))
      (node (ref "C18") (pin "1") (pinfunction "1_1") (pintype "passive"))
      (node (ref "C19") (pin "1") (pinfunction "1_1") (pintype "passive"))
      (node (ref "C20") (pin "2") (pinfunction "2_2") (pintype "passive"))
      (node (ref "C21") (pin "1") (pinfunction "1_1") (pintype "passive"))
      (node (ref "C22") (pin "1") (pinfunction "1_1") (pintype "passive"))
      (node (ref "C23") (pin "1") (pinfunction "1_1") (pintype "passive"))
      (node (ref "C24") (pin "1") (pinfunction "1_1") (pintype "passive"))
      (node (ref "C25") (pin "1") (pinfunction "1_1") (pintype "passive"))
      (node (ref "C26") (pin "1") (pinfunction "1_1") (pintype "passive"))
      (node (ref "C27") (pin "1") (pinfunction "1_1") (pintype "passive"))
      (node (ref "C29") (pin "2") (pinfunction "2_2") (pintype "passive"))
      (node (ref "C30") (pin "2") (pinfunction "2_2") (pintype "passive"))
      (node (ref "C31") (pin "2") (pinfunction "2_2") (pintype "passive"))
      (node (ref "C40") (pin "1") (pinfunction "1_1") (pintype "passive"))
      (node (ref "C44") (pin "1") (pinfunction "1_1") (pintype "passive"))
      (node (ref "C47") (pin "1") (pinfunction "1_1") (pintype "passive"))
      (node (ref "C51") (pin "2") (pinfunction "2_2") (pintype "passive"))
      (node (ref "C52") (pin "2") (pinfunction "2_2") (pintype "passive"))
      (node (ref "C53") (pin "1") (pinfunction "1_1") (pintype "passive"))
      (node (ref "C54") (pin "2") (pinfunction "2_2") (pintype "passive"))
      (node (ref "C58") (pin "1") (pinfunction "1_1") (pintype "passive"))
      (node (ref "C59") (pin "1") (pinfunction "1_1") (pintype "passive"))
      (node (ref "C60") (pin "1") (pinfunction "1_1") (pintype "passive"))
      (node (ref "CON1") (pin "10") (pinfunction "10_10") (pintype "passive"))
      (node (ref "CON2") (pin "17") (pinfunction "BS_17") (pintype "passive"))
      (node (ref "CON2") (pin "8") (pinfunction "VSS_8") (pintype "passive"))
      (node (ref "D1") (pin "K") (pinfunction "K_K") (pintype "passive"))
      (node (ref "Q4") (pin "2") (pinfunction "D_2") (pintype "passive"))
      (node (ref "R10") (pin "2") (pinfunction "2_2") (pintype "passive"))
      (node (ref "R6") (pin "2") (pinfunction "2_2") (pintype "passive"))
      (node (ref "R7") (pin "2") (pinfunction "2_2") (pintype "passive"))
      (node (ref "R8") (pin "2") (pinfunction "2_2") (pintype "passive"))
      (node (ref "R9") (pin "1") (pinfunction "1_1") (pintype "passive"))
      (node (ref "SD1") (pin "10") (pinfunction "CD2_10") (pintype "passive"))
      (node (ref "SD1") (pin "11") (pinfunction "fix_11") (pintype "passive"))
      (node (ref "SD1") (pin "6") (pinfunction "VSS_6") (pintype "passive"))
      (node (ref "U1") (pin "18") (pinfunction "GND_18") (pintype "passive"))
      (node (ref "U1") (pin "35") (pinfunction "GND_35") (pintype "passive"))
      (node (ref "U1") (pin "42") (pinfunction "GND_42") (pintype "passive"))
      (node (ref "U1") (pin "5") (pinfunction "GNDANA_5") (pintype "passive"))
      (node (ref "U10") (pin "1") (pinfunction "1_1") (pintype "passive"))
      (node (ref "U15") (pin "1") (pinfunction "1_1") (pintype "passive"))
      (node (ref "U16") (pin "2") (pinfunction "V-_2") (pintype "passive"))
      (node (ref "U17") (pin "1") (pinfunction "1_1") (pintype "passive"))
      (node (ref "U2") (pin "28") (pinfunction "TEST_28") (pintype "passive"))
      (node (ref "U2") (pin "30") (pinfunction "SD_WP_30") (pintype "passive"))
      (node (ref "U2") (pin "PAD") (pinfunction "VSS_PAD") (pintype "passive"))
      (node (ref "U3") (pin "2") (pinfunction "GND_2") (pintype "passive"))
      (node (ref "U4") (pin "3") (pinfunction "GND_3") (pintype "power_in"))
      (node (ref "U7") (pin "1") (pinfunction "1_1") (pintype "passive"))
      (node (ref "USB_PROG") (pin "5") (pinfunction "GND_5") (pintype "passive"))
      (node (ref "USB_PROG") (pin "6") (pinfunction "SHLD_6") (pintype "passive"))
      (node (ref "USB_SD") (pin "4") (pinfunction "ID_4") (pintype "passive"))
      (node (ref "USB_SD") (pin "5") (pinfunction "GND_5") (pintype "passive"))
      (node (ref "USB_SD") (pin "6") (pinfunction "SHLD_6") (pintype "passive"))
      (node (ref "X2") (pin "2") (pinfunction "2_2") (pintype "passive"))
      (node (ref "X2") (pin "4") (pinfunction "4_4") (pintype "passive"))
    )
    (net (code "68") (name "Net-(C48-Pad2)") (class "Default")
      (node (ref "C48") (pin "2") (pinfunction "2_2") (pintype "passive"))
      (node (ref "D1") (pin "A") (pinfunction "A_A") (pintype "passive"))
      (node (ref "D2") (pin "K") (pinfunction "K_K") (pintype "passive"))
    )
    (net (code "69") (name "Net-(CON2-VCOM)") (class "Default")
      (node (ref "C19") (pin "2") (pinfunction "2_2") (pintype "passive"))
      (node (ref "CON2") (pin "1") (pinfunction "VCOM_1") (pintype "passive"))
    )
    (net (code "70") (name "Net-(CON2-VDD)") (class "Default")
      (node (ref "C12") (pin "2") (pinfunction "2_2") (pintype "passive"))
      (node (ref "CON2") (pin "7") (pinfunction "VDD_7") (pintype "passive"))
    )
    (net (code "71") (name "Net-(CON2-VGH)") (class "Default")
      (node (ref "C44") (pin "2") (pinfunction "2_2") (pintype "passive"))
      (node (ref "CON2") (pin "20") (pinfunction "VGH_20") (pintype "passive"))
    )
    (net (code "72") (name "Net-(CON2-VGL)") (class "Default")
      (node (ref "C40") (pin "2") (pinfunction "2_2") (pintype "passive"))
      (node (ref "CON2") (pin "21") (pinfunction "VGL_21") (pintype "passive"))
    )
    (net (code "73") (name "Net-(CON2-VPP)") (class "Default")
      (node (ref "C14") (pin "2") (pinfunction "2_2") (pintype "passive"))
      (node (ref "CON2") (pin "6") (pinfunction "VPP_6") (pintype "passive"))
    )
    (net (code "74") (name "Net-(CON2-VSH)") (class "Default")
      (node (ref "C15") (pin "2") (pinfunction "2_2") (pintype "passive"))
      (node (ref "CON2") (pin "5") (pinfunction "VSH_5") (pintype "passive"))
    )
    (net (code "75") (name "Net-(CON2-VSL)") (class "Default")
      (node (ref "C17") (pin "2") (pinfunction "2_2") (pintype "passive"))
      (node (ref "CON2") (pin "3") (pinfunction "VSL_3") (pintype "passive"))
    )
    (net (code "76") (name "Net-(D9-Pad2)") (class "Default")
      (node (ref "D9") (pin "2") (pinfunction "2_2") (pintype "passive"))
      (node (ref "R9") (pin "2") (pinfunction "2_2") (pintype "passive"))
    )
    (net (code "77") (name "Net-(Q1-S)") (class "Default")
      (node (ref "C48") (pin "1") (pinfunction "1_1") (pintype "passive"))
      (node (ref "D3") (pin "A") (pinfunction "A_A") (pintype "passive"))
      (node (ref "L1") (pin "2") (pinfunction "2_2") (pintype "passive"))
      (node (ref "Q1") (pin "3") (pinfunction "S_3") (pintype "passive"))
    )
    (net (code "78") (name "Net-(Q2-D)") (class "Default")
      (node (ref "C27") (pin "2") (pinfunction "2_2") (pintype "passive"))
      (node (ref "Q2") (pin "3") (pinfunction "D_3") (pintype "passive"))
      (node (ref "SD1") (pin "4") (pinfunction "VDD_4") (pintype "passive"))
      (node (ref "U2") (pin "21") (pinfunction "CRD_PWR_21") (pintype "passive"))
    )
    (net (code "79") (name "Net-(Q4-S)") (class "Default")
      (node (ref "CON_HEAT") (pin "2") (pinfunction "2_2") (pintype "passive"))
      (node (ref "Q4") (pin "3") (pinfunction "S_3") (pintype "passive"))
    )
    (net (code "80") (name "Net-(U1-PA00)") (class "Default")
      (node (ref "C30") (pin "1") (pinfunction "1_1") (pintype "passive"))
      (node (ref "U1") (pin "1") (pinfunction "PA00_1") (pintype "passive"))
      (node (ref "X1") (pin "2") (pinfunction "2_2") (pintype "passive"))
    )
    (net (code "81") (name "Net-(U1-PA01)") (class "Default")
      (node (ref "C31") (pin "1") (pinfunction "1_1") (pintype "passive"))
      (node (ref "U1") (pin "2") (pinfunction "PA01_2") (pintype "passive"))
      (node (ref "X1") (pin "1") (pinfunction "1_1") (pintype "passive"))
    )
    (net (code "82") (name "Net-(U2-RBIAS)") (class "Default")
      (node (ref "R10") (pin "1") (pinfunction "1_1") (pintype "passive"))
      (node (ref "U2") (pin "35") (pinfunction "RBIAS_35") (pintype "passive"))
    )
    (net (code "83") (name "Net-(U2-USB+)") (class "Default")
      (node (ref "U2") (pin "2") (pinfunction "USB+_2") (pintype "passive"))
      (node (ref "U3") (pin "3") (pinfunction "IO2_3") (pintype "passive"))
      (node (ref "USB_SD") (pin "3") (pinfunction "D+_3") (pintype "passive"))
    )
    (net (code "84") (name "Net-(U2-USB-)") (class "Default")
      (node (ref "U2") (pin "3") (pinfunction "USB-_3") (pintype "passive"))
      (node (ref "U3") (pin "4") (pinfunction "IO3_4") (pintype "passive"))
      (node (ref "USB_SD") (pin "2") (pinfunction "D-_2") (pintype "passive"))
    )
    (net (code "85") (name "Net-(U2-VDD18)") (class "Default")
      (node (ref "C25") (pin "2") (pinfunction "2_2") (pintype "passive"))
      (node (ref "U2") (pin "13") (pinfunction "VDD18_13") (pintype "passive"))
    )
    (net (code "86") (name "Net-(U2-VDD18PLL)") (class "Default")
      (node (ref "C26") (pin "2") (pinfunction "2_2") (pintype "passive"))
      (node (ref "U2") (pin "34") (pinfunction "VDD18PLL_34") (pintype "passive"))
    )
    (net (code "87") (name "Net-(U2-XTAL1(CLKIN))") (class "Default")
      (node (ref "C20") (pin "1") (pinfunction "1_1") (pintype "passive"))
      (node (ref "R3") (pin "2") (pinfunction "2_2") (pintype "passive"))
      (node (ref "U2") (pin "33") (pinfunction "XTAL1(CLKIN)_33") (pintype "passive"))
      (node (ref "X2") (pin "1") (pinfunction "1_1") (pintype "passive"))
    )
    (net (code "88") (name "Net-(U2-XTAL2)") (class "Default")
      (node (ref "C29") (pin "1") (pinfunction "1_1") (pintype "passive"))
      (node (ref "R3") (pin "1") (pinfunction "1_1") (pintype "passive"))
      (node (ref "U2") (pin "32") (pinfunction "XTAL2_32") (pintype "passive"))
      (node (ref "X2") (pin "3") (pinfunction "3_3") (pintype "passive"))
    )
    (net (code "89") (name "Net-(U16--)") (class "Default")
      (node (ref "R18") (pin "1") (pinfunction "1_1") (pintype "passive"))
      (node (ref "U16") (pin "1") (pinfunction "Out_A_1") (pintype "passive"))
      (node (ref "U16") (pin "4") (pinfunction "-_4") (pintype "passive"))
    )
    (net (code "90") (name "VUSB") (class "Default")
      (node (ref "U3") (pin "5") (pinfunction "VBUS_5") (pintype "passive"))
      (node (ref "USB_SD") (pin "1") (pinfunction "VCC_1") (pintype "passive"))
    )
    (net (code "91") (name "VUSB_PROG") (class "Default")
      (node (ref "D11") (pin "K") (pinfunction "K_K") (pintype "passive"))
      (node (ref "USB_PROG") (pin "1") (pinfunction "VCC_1") (pintype "passive"))
    )
    (net (code "92") (name "unconnected-(CON1-Pad2)") (class "Default")
      (node (ref "CON1") (pin "2") (pinfunction "2_2") (pintype "passive"))
    )
    (net (code "93") (name "unconnected-(CON1-Pad4)") (class "Default")
      (node (ref "CON1") (pin "4") (pinfunction "4_4") (pintype "passive"))
    )
    (net (code "94") (name "unconnected-(CON1-Pad5)") (class "Default")
      (node (ref "CON1") (pin "5") (pinfunction "5_5") (pintype "passive"))
    )
    (net (code "95") (name "unconnected-(CON1-Pad6)") (class "Default")
      (node (ref "CON1") (pin "6") (pinfunction "6_6") (pintype "passive"))
    )
    (net (code "96") (name "unconnected-(CON1-Pad7)") (class "Default")
      (node (ref "CON1") (pin "7") (pinfunction "7_7") (pintype "passive"))
    )
    (net (code "97") (name "unconnected-(CON2-HLT_CTL-Pad24)") (class "Default")
      (node (ref "CON2") (pin "24") (pinfunction "HLT_CTL_24") (pintype "passive"))
    )
    (net (code "98") (name "unconnected-(CON2-TSCL-Pad19)") (class "Default")
      (node (ref "CON2") (pin "19") (pinfunction "TSCL_19") (pintype "passive"))
    )
    (net (code "99") (name "unconnected-(CON2-TSDA-Pad18)") (class "Default")
      (node (ref "CON2") (pin "18") (pinfunction "TSDA_18") (pintype "passive"))
    )
    (net (code "100") (name "unconnected-(U2-LED-Pad1)") (class "Default")
      (node (ref "U2") (pin "1") (pinfunction "LED_1") (pintype "passive"))
    )
    (net (code "101") (name "unconnected-(U2-NC-Pad12)") (class "Default")
      (node (ref "U2") (pin "12") (pinfunction "NC_12") (pintype "passive"))
    )
    (net (code "102") (name "unconnected-(U2-NC-Pad15)") (class "Default")
      (node (ref "U2") (pin "15") (pinfunction "NC_15") (pintype "passive"))
    )
    (net (code "103") (name "unconnected-(U2-NC-Pad16)") (class "Default")
      (node (ref "U2") (pin "16") (pinfunction "NC_16") (pintype "passive"))
    )
    (net (code "104") (name "unconnected-(U2-NC-Pad17)") (class "Default")
      (node (ref "U2") (pin "17") (pinfunction "NC_17") (pintype "passive"))
    )
    (net (code "105") (name "unconnected-(U2-NC-Pad19)") (class "Default")
      (node (ref "U2") (pin "19") (pinfunction "NC_19") (pintype "passive"))
    )
    (net (code "106") (name "unconnected-(U2-NC-Pad24)") (class "Default")
      (node (ref "U2") (pin "24") (pinfunction "NC_24") (pintype "passive"))
    )
    (net (code "107") (name "unconnected-(U2-NC-Pad29)") (class "Default")
      (node (ref "U2") (pin "29") (pinfunction "NC_29") (pintype "passive"))
    )
    (net (code "108") (name "unconnected-(U2-RXD{slash}SDA-Pad27)") (class "Default")
      (node (ref "U2") (pin "27") (pinfunction "RXD/SDA_27") (pintype "passive"))
    )
    (net (code "109") (name "unconnected-(U2-SD_D4-Pad20)") (class "Default")
      (node (ref "U2") (pin "20") (pinfunction "SD_D4_20") (pintype "passive"))
    )
    (net (code "110") (name "unconnected-(U2-SD_D5-Pad10)") (class "Default")
      (node (ref "U2") (pin "10") (pinfunction "SD_D5_10") (pintype "passive"))
    )
    (net (code "111") (name "unconnected-(U2-SD_D6-Pad8)") (class "Default")
      (node (ref "U2") (pin "8") (pinfunction "SD_D6_8") (pintype "passive"))
    )
    (net (code "112") (name "unconnected-(U2-SD_D7-Pad7)") (class "Default")
      (node (ref "U2") (pin "7") (pinfunction "SD_D7_7") (pintype "passive"))
    )
    (net (code "113") (name "unconnected-(U2-TXD{slash}SCK-Pad31)") (class "Default")
      (node (ref "U2") (pin "31") (pinfunction "TXD/SCK_31") (pintype "passive"))
    )
    (net (code "114") (name "unconnected-(U3-IO1-Pad1)") (class "Default")
      (node (ref "U3") (pin "1") (pinfunction "IO1_1") (pintype "passive"))
    )
    (net (code "115") (name "unconnected-(U3-IO4-Pad6)") (class "Default")
      (node (ref "U3") (pin "6") (pinfunction "IO4_6") (pintype "passive"))
    )
    (net (code "116") (name "unconnected-(U4B-NC-Pad1)") (class "Default")
      (node (ref "U4") (pin "1") (pinfunction "NC_1") (pintype "passive"))
    )
    (net (code "117") (name "unconnected-(USB_PROG-ID-Pad4)") (class "Default")
      (node (ref "USB_PROG") (pin "4") (pinfunction "ID_4") (pintype "passive"))
    )
  )
)
